# 1-Schematic_submit.net
KiCad netlist of a schematic drawn in EasyEDA
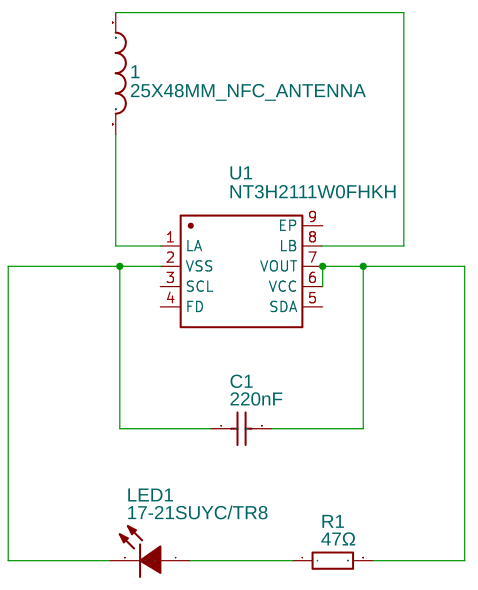
[diagram p0: schematic sheet]

(export (version "E")
  (design (tool "Eeschema 10.0.6"))
  (components
    (comp (ref "1") (value "25X48MM_NFC_ANTENNA") (libsource (lib "") (part "25X48MM_NFC_ANTENNA")))
    (comp (ref "C1")
      (value "220nF")
      (fields
        (field (name "BOM_Manufacturer Part") "CL10B224KA8NNNC")
        (field (name "BOM_Supplier Part") "C21120")
      )
      (libsource (lib "") (part "CL10B224KA8NNNC"))
    )
    (comp (ref "LED1")
      (value "17-21SUYC/TR8")
      (fields (field (name "BOM_Manufacturer Part") "KT-0805黄灯") (field (name "BOM_Supplier Part") "C2296"))
      (libsource (lib "") (part "17-21SUYC/TR8"))
    )
    (comp (ref "R1")
      (value "47Ω")
      (fields
        (field (name "BOM_Manufacturer Part") "0603WAF470JT5E")
        (field (name "BOM_Supplier Part") "C23182")
      )
      (libsource (lib "") (part "0603WAF470JT5E"))
    )
    (comp (ref "U1")
      (value "NT3H2111W0FHKH")
      (fields (field (name "BOM_Supplier Part") "C710403"))
      (libsource (lib "") (part "NT3H2111W0FHKH"))
    )
  )
  (nets
    (net (code "1") (name "Net-(LED1-+)") (class "Default")
      (node (ref "LED1") (pin "1") (pinfunction "+_1") (pintype "unspecified"))
      (node (ref "R1") (pin "1") (pinfunction "1_1") (pintype "input"))
    )
    (net (code "2") (name "Net-(LED1--)") (class "Default")
      (node (ref "C1") (pin "1") (pinfunction "1_1") (pintype "input"))
      (node (ref "LED1") (pin "2") (pinfunction "-_2") (pintype "unspecified"))
      (node (ref "U1") (pin "2") (pinfunction "VSS_2") (pintype "unspecified"))
    )
    (net (code "3") (name "Net-(U1-LA)") (class "Default")
      (node (ref "1") (pin "P$2") (pinfunction "P$2_P$2") (pintype "bidirectional"))
      (node (ref "U1") (pin "1") (pinfunction "LA_1") (pintype "unspecified"))
    )
    (net (code "4") (name "Net-(U1-LB)") (class "Default")
      (node (ref "1") (pin "P$1") (pinfunction "P$1_P$1") (pintype "bidirectional"))
      (node (ref "U1") (pin "8") (pinfunction "LB_8") (pintype "unspecified"))
    )
    (net (code "5") (name "Net-(U1-VCC)") (class "Default")
      (node (ref "C1") (pin "2") (pinfunction "2_2") (pintype "input"))
      (node (ref "R1") (pin "2") (pinfunction "2_2") (pintype "input"))
      (node (ref "U1") (pin "6") (pinfunction "VCC_6") (pintype "unspecified"))
      (node (ref "U1") (pin "7") (pinfunction "VOUT_7") (pintype "unspecified"))
    )
    (net (code "6") (name "unconnected-(U1-EP-Pad9)") (class "Default")
      (node (ref "U1") (pin "9") (pinfunction "EP_9") (pintype "unspecified"))
    )
    (net (code "7") (name "unconnected-(U1-FD-Pad4)") (class "Default")
      (node (ref "U1") (pin "4") (pinfunction "FD_4") (pintype "unspecified"))
    )
    (net (code "8") (name "unconnected-(U1-SCL-Pad3)") (class "Default")
      (node (ref "U1") (pin "3") (pinfunction "SCL_3") (pintype "unspecified"))
    )
    (net (code "9") (name "unconnected-(U1-SDA-Pad5)") (class "Default")
      (node (ref "U1") (pin "5") (pinfunction "SDA_5") (pintype "unspecified"))
    )
  )
)
